# UPTC.net
KiCad netlist of a schematic drawn in EAGLE
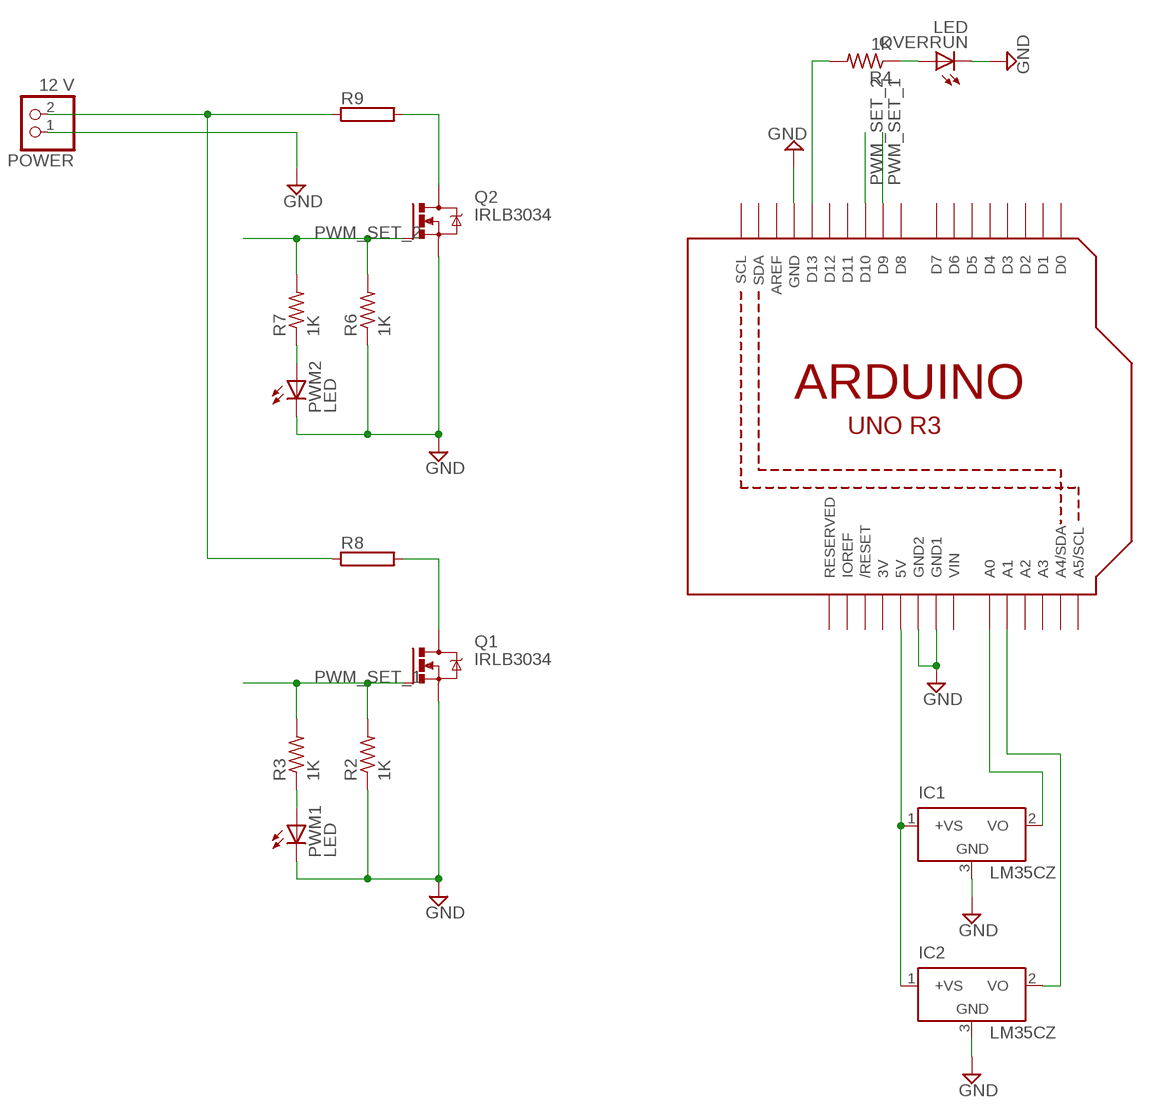
[diagram p0: schematic, sheet 1]

(export (version "E")
  (design (tool "Eeschema 10.0.6"))
  (components
    (comp (ref "IC1")
      (value "LM35CZ")
      (footprint "eagle-import:TO92")
      (libsource (lib "eagle-import") (part "LM35CZ"))
    )
    (comp (ref "IC2")
      (value "LM35CZ")
      (footprint "eagle-import:TO92")
      (libsource (lib "eagle-import") (part "LM35CZ"))
    )
    (comp (ref "OVERRUN")
      (value "LED")
      (footprint "eagle-import:LED5MM")
      (libsource (lib "eagle-import") (part "LED5MM"))
    )
    (comp (ref "POWER")
      (value "12 V")
      (footprint "eagle-import:1X02")
      (libsource (lib "eagle-import") (part "PINHD-1X2"))
    )
    (comp (ref "PWM1")
      (value "LED")
      (footprint "eagle-import:LED5MM")
      (libsource (lib "eagle-import") (part "LED5MM"))
    )
    (comp (ref "PWM2")
      (value "LED")
      (footprint "eagle-import:LED5MM")
      (libsource (lib "eagle-import") (part "LED5MM"))
    )
    (comp (ref "Q1")
      (value "IRLB3034")
      (footprint "eagle-import:TO220BV")
      (libsource (lib "eagle-import") (part "IRF520"))
    )
    (comp (ref "Q2")
      (value "IRLB3034")
      (footprint "eagle-import:TO220BV")
      (libsource (lib "eagle-import") (part "IRF520"))
    )
    (comp (ref "R2")
      (value "1K")
      (footprint "eagle-import:0207_10")
      (libsource (lib "eagle-import") (part "R-US_0207/10"))
    )
    (comp (ref "R3")
      (value "1K")
      (footprint "eagle-import:0207_10")
      (libsource (lib "eagle-import") (part "R-US_0207/10"))
    )
    (comp (ref "R4")
      (value "1K")
      (footprint "eagle-import:0207_10")
      (libsource (lib "eagle-import") (part "R-US_0207/10"))
    )
    (comp (ref "R6")
      (value "1K")
      (footprint "eagle-import:0207_10")
      (libsource (lib "eagle-import") (part "R-US_0207/10"))
    )
    (comp (ref "R7")
      (value "1K")
      (footprint "eagle-import:0207_10")
      (libsource (lib "eagle-import") (part "R-US_0207/10"))
    )
    (comp (ref "R8")
      (value "RAC05")
      (footprint "eagle-import:AC05")
      (libsource (lib "eagle-import") (part "RAC05"))
    )
    (comp (ref "R9")
      (value "RAC05")
      (footprint "eagle-import:AC05")
      (libsource (lib "eagle-import") (part "RAC05"))
    )
    (comp (ref "U2")
      (value "ARDUINOR3-BPLACE")
      (footprint "eagle-import:ARDUINOR3-BPLACE")
      (libsource (lib "eagle-import") (part "ARDUINOR3-BPLACE"))
    )
  )
  (nets
    (net (code "1") (name "/3V") (class "Default")
      (node (ref "U2") (pin "3V") (pinfunction "3V_3V") (pintype "power_in"))
    )
    (net (code "2") (name "/PWM_SET_1") (class "Default")
      (node (ref "Q1") (pin "G") (pinfunction "G_G") (pintype "passive"))
      (node (ref "R2") (pin "2") (pinfunction "2_2") (pintype "passive"))
      (node (ref "R3") (pin "2") (pinfunction "2_2") (pintype "passive"))
      (node (ref "U2") (pin "D9") (pinfunction "D9_D9") (pintype "bidirectional"))
    )
    (net (code "3") (name "/PWM_SET_2") (class "Default")
      (node (ref "Q2") (pin "G") (pinfunction "G_G") (pintype "passive"))
      (node (ref "R6") (pin "2") (pinfunction "2_2") (pintype "passive"))
      (node (ref "R7") (pin "2") (pinfunction "2_2") (pintype "passive"))
      (node (ref "U2") (pin "D10") (pinfunction "D10_D10") (pintype "bidirectional"))
    )
    (net (code "4") (name "/VIN") (class "Default")
      (node (ref "U2") (pin "VIN") (pinfunction "VIN_VIN") (pintype "power_in"))
    )
    (net (code "5") (name "GND") (class "Default")
      (node (ref "IC1") (pin "3") (pinfunction "GND_3") (pintype "power_in"))
      (node (ref "IC2") (pin "3") (pinfunction "GND_3") (pintype "power_in"))
      (node (ref "OVERRUN") (pin "K") (pinfunction "C_K") (pintype "passive"))
      (node (ref "POWER") (pin "1") (pinfunction "1_1") (pintype "passive"))
      (node (ref "PWM1") (pin "K") (pinfunction "C_K") (pintype "passive"))
      (node (ref "PWM2") (pin "K") (pinfunction "C_K") (pintype "passive"))
      (node (ref "Q1") (pin "S") (pinfunction "S_S") (pintype "passive"))
      (node (ref "Q2") (pin "S") (pinfunction "S_S") (pintype "passive"))
      (node (ref "R2") (pin "1") (pinfunction "1_1") (pintype "passive"))
      (node (ref "R6") (pin "1") (pinfunction "1_1") (pintype "passive"))
      (node (ref "U2") (pin "GND") (pinfunction "GND_GND") (pintype "power_in"))
      (node (ref "U2") (pin "GND1") (pinfunction "GND1_GND1") (pintype "power_in"))
      (node (ref "U2") (pin "GND2") (pinfunction "GND2_GND2") (pintype "power_in"))
    )
    (net (code "6") (name "Net-(IC1-+VS)") (class "Default")
      (node (ref "IC1") (pin "1") (pinfunction "+VS_1") (pintype "input"))
      (node (ref "IC2") (pin "1") (pinfunction "+VS_1") (pintype "input"))
      (node (ref "U2") (pin "5V") (pinfunction "5V_5V") (pintype "power_in"))
    )
    (net (code "7") (name "Net-(IC1-VO)") (class "Default")
      (node (ref "IC1") (pin "2") (pinfunction "VO_2") (pintype "input"))
      (node (ref "U2") (pin "A0") (pinfunction "A0_A0") (pintype "bidirectional"))
    )
    (net (code "8") (name "Net-(IC2-VO)") (class "Default")
      (node (ref "IC2") (pin "2") (pinfunction "VO_2") (pintype "input"))
      (node (ref "U2") (pin "A1") (pinfunction "A1_A1") (pintype "bidirectional"))
    )
    (net (code "9") (name "Net-(OVERRUN-PadA)") (class "Default")
      (node (ref "OVERRUN") (pin "A") (pinfunction "A_A") (pintype "passive"))
      (node (ref "R4") (pin "1") (pinfunction "1_1") (pintype "passive"))
    )
    (net (code "10") (name "Net-(POWER-Pad2)") (class "Default")
      (node (ref "POWER") (pin "2") (pinfunction "2_2") (pintype "passive"))
      (node (ref "R8") (pin "1") (pinfunction "1_1") (pintype "passive"))
      (node (ref "R9") (pin "1") (pinfunction "1_1") (pintype "passive"))
    )
    (net (code "11") (name "Net-(PWM1-PadA)") (class "Default")
      (node (ref "PWM1") (pin "A") (pinfunction "A_A") (pintype "passive"))
      (node (ref "R3") (pin "1") (pinfunction "1_1") (pintype "passive"))
    )
    (net (code "12") (name "Net-(PWM2-PadA)") (class "Default")
      (node (ref "PWM2") (pin "A") (pinfunction "A_A") (pintype "passive"))
      (node (ref "R7") (pin "1") (pinfunction "1_1") (pintype "passive"))
    )
    (net (code "13") (name "Net-(Q1-PadD)") (class "Default")
      (node (ref "Q1") (pin "D") (pinfunction "D_D") (pintype "passive"))
      (node (ref "R8") (pin "2") (pinfunction "2_2") (pintype "passive"))
    )
    (net (code "14") (name "Net-(Q2-PadD)") (class "Default")
      (node (ref "Q2") (pin "D") (pinfunction "D_D") (pintype "passive"))
      (node (ref "R9") (pin "2") (pinfunction "2_2") (pintype "passive"))
    )
    (net (code "15") (name "Net-(R4-Pad2)") (class "Default")
      (node (ref "R4") (pin "2") (pinfunction "2_2") (pintype "passive"))
      (node (ref "U2") (pin "D13") (pinfunction "D13_D13") (pintype "bidirectional"))
    )
    (net (code "16") (name "unconnected-(U2-A4{slash}SDA-PadA4)") (class "Default")
      (node (ref "U2") (pin "A4") (pinfunction "A4/SDA_A4") (pintype "bidirectional"))
    )
    (net (code "17") (name "unconnected-(U2-A5{slash}SCL-PadA5)") (class "Default")
      (node (ref "U2") (pin "A5") (pinfunction "A5/SCL_A5") (pintype "bidirectional"))
    )
    (net (code "18") (name "unconnected-(U2-PadA2)") (class "Default")
      (node (ref "U2") (pin "A2") (pinfunction "A2_A2") (pintype "bidirectional"))
    )
    (net (code "19") (name "unconnected-(U2-PadA3)") (class "Default")
      (node (ref "U2") (pin "A3") (pinfunction "A3_A3") (pintype "bidirectional"))
    )
    (net (code "20") (name "unconnected-(U2-PadAREF)") (class "Default")
      (node (ref "U2") (pin "AREF") (pinfunction "AREF_AREF") (pintype "bidirectional"))
    )
    (net (code "21") (name "unconnected-(U2-PadD0)") (class "Default")
      (node (ref "U2") (pin "D0") (pinfunction "D0_D0") (pintype "bidirectional"))
    )
    (net (code "22") (name "unconnected-(U2-PadD1)") (class "Default")
      (node (ref "U2") (pin "D1") (pinfunction "D1_D1") (pintype "bidirectional"))
    )
    (net (code "23") (name "unconnected-(U2-PadD2)") (class "Default")
      (node (ref "U2") (pin "D2") (pinfunction "D2_D2") (pintype "bidirectional"))
    )
    (net (code "24") (name "unconnected-(U2-PadD3)") (class "Default")
      (node (ref "U2") (pin "D3") (pinfunction "D3_D3") (pintype "bidirectional"))
    )
    (net (code "25") (name "unconnected-(U2-PadD4)") (class "Default")
      (node (ref "U2") (pin "D4") (pinfunction "D4_D4") (pintype "bidirectional"))
    )
    (net (code "26") (name "unconnected-(U2-PadD5)") (class "Default")
      (node (ref "U2") (pin "D5") (pinfunction "D5_D5") (pintype "bidirectional"))
    )
    (net (code "27") (name "unconnected-(U2-PadD6)") (class "Default")
      (node (ref "U2") (pin "D6") (pinfunction "D6_D6") (pintype "bidirectional"))
    )
    (net (code "28") (name "unconnected-(U2-PadD7)") (class "Default")
      (node (ref "U2") (pin "D7") (pinfunction "D7_D7") (pintype "bidirectional"))
    )
    (net (code "29") (name "unconnected-(U2-PadD8)") (class "Default")
      (node (ref "U2") (pin "D8") (pinfunction "D8_D8") (pintype "bidirectional"))
    )
    (net (code "30") (name "unconnected-(U2-PadD11)") (class "Default")
      (node (ref "U2") (pin "D11") (pinfunction "D11_D11") (pintype "bidirectional"))
    )
    (net (code "31") (name "unconnected-(U2-PadD12)") (class "Default")
      (node (ref "U2") (pin "D12") (pinfunction "D12_D12") (pintype "bidirectional"))
    )
    (net (code "32") (name "unconnected-(U2-PadIOREF)") (class "Default")
      (node (ref "U2") (pin "IOREF") (pinfunction "IOREF_IOREF") (pintype "output"))
    )
    (net (code "33") (name "unconnected-(U2-PadRESERVED)") (class "Default")
      (node (ref "U2") (pin "RESERVED") (pinfunction "RESERVED_RESERVED") (pintype "no_connect"))
    )
    (net (code "34") (name "unconnected-(U2-PadSCL)") (class "Default")
      (node (ref "U2") (pin "SCL") (pinfunction "SCL_SCL") (pintype "bidirectional"))
    )
    (net (code "35") (name "unconnected-(U2-PadSDA)") (class "Default")
      (node (ref "U2") (pin "SDA") (pinfunction "SDA_SDA") (pintype "bidirectional"))
    )
    (net (code "36") (name "unconnected-(U2-{slash}RESET-PadRESET)") (class "Default")
      (node (ref "U2") (pin "RESET") (pinfunction "/RESET_RESET") (pintype "bidirectional"))
    )
  )
)
